# EEPROM_FLASH.net
KiCad netlist of a schematic drawn in Altium Designer
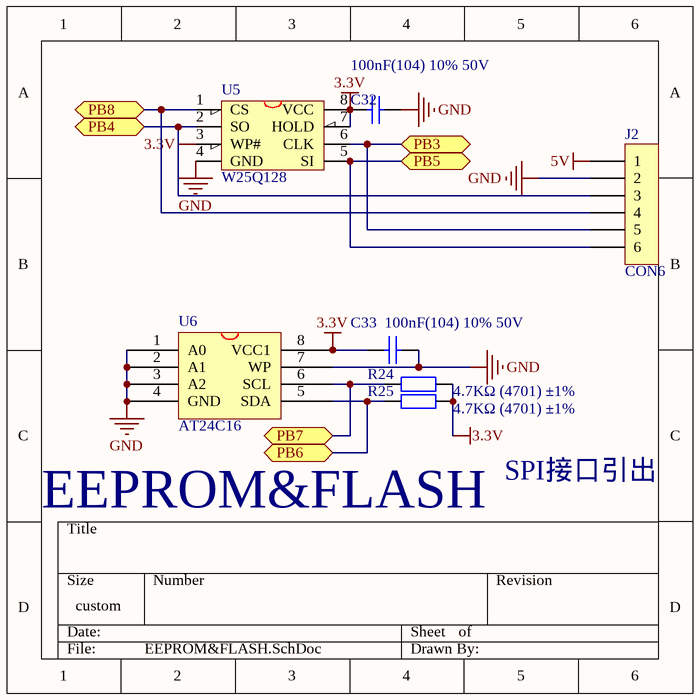
[diagram p0: EEPROM&FLASH.SchDoc]

(export (version "E")
  (design (tool "Eeschema 10.0.6"))
  (components
    (comp (ref "C32")
      (value "100nF(104) 10% 50V")
      (footprint "0805_C")
      (description "贴片电容")
      (libsource (lib "Cap") (part "0805 100nF(104) 10% 50V"))
    )
    (comp (ref "C33")
      (value "100nF(104) 10% 50V")
      (footprint "0805_C")
      (description "贴片电容")
      (libsource (lib "Cap") (part "0805 100nF(104) 10% 50V"))
    )
    (comp (ref "J2")
      (value "CON6")
      (footprint "Connector:XH2.54-6P")
      (description "连接器")
      (libsource (lib "Connector") (part "CON6"))
    )
    (comp (ref "R24")
      (value "4.7KΩ (4701) ±1%")
      (footprint "0805_R")
      (description "贴片电阻")
      (libsource (lib "RES") (part "0805 4.7KΩ (4701) 1%"))
    )
    (comp (ref "R25")
      (value "4.7KΩ (4701) ±1%")
      (footprint "0805_R")
      (description "贴片电阻")
      (libsource (lib "RES") (part "0805 4.7KΩ (4701) 1%"))
    )
    (comp (ref "U5")
      (value "W25Q128")
      (footprint "SOIC-8")
      (description "W25X16;SST25VF016;MX25L1605")
      (libsource (lib "EXPLORER") (part "W25X16"))
    )
    (comp (ref "U6") (value "AT24C16") (footprint "SOP-8") (libsource (lib "EXPLORER") (part "24C256")))
  )
  (nets
    (net (code "1") (name "/PB3") (class "Default")
      (node (ref "J2") (pin "5") (pinfunction "5_5") (pintype "passive"))
      (node (ref "U5") (pin "6") (pinfunction "CLK_6") (pintype "passive"))
    )
    (net (code "2") (name "/PB4") (class "Default")
      (node (ref "J2") (pin "3") (pinfunction "3_3") (pintype "passive"))
      (node (ref "U5") (pin "2") (pinfunction "SO_2") (pintype "passive"))
    )
    (net (code "3") (name "/PB5") (class "Default")
      (node (ref "J2") (pin "6") (pinfunction "6_6") (pintype "passive"))
      (node (ref "U5") (pin "5") (pinfunction "SI_5") (pintype "passive"))
    )
    (net (code "4") (name "/PB6") (class "Default")
      (node (ref "R25") (pin "1") (pinfunction "1_1") (pintype "passive"))
      (node (ref "U6") (pin "5") (pinfunction "SDA_5") (pintype "passive"))
    )
    (net (code "5") (name "/PB7") (class "Default")
      (node (ref "R24") (pin "1") (pinfunction "1_1") (pintype "passive"))
      (node (ref "U6") (pin "6") (pinfunction "SCL_6") (pintype "passive"))
    )
    (net (code "6") (name "/PB8") (class "Default")
      (node (ref "J2") (pin "4") (pinfunction "4_4") (pintype "passive"))
      (node (ref "U5") (pin "1") (pinfunction "CS_1") (pintype "passive"))
    )
    (net (code "7") (name "3.3V") (class "Default")
      (node (ref "C32") (pin "1") (pinfunction "1_1") (pintype "passive"))
      (node (ref "C33") (pin "1") (pinfunction "1_1") (pintype "passive"))
      (node (ref "R24") (pin "2") (pinfunction "2_2") (pintype "passive"))
      (node (ref "R25") (pin "2") (pinfunction "2_2") (pintype "passive"))
      (node (ref "U5") (pin "3") (pinfunction "WP#_3") (pintype "passive"))
      (node (ref "U5") (pin "7") (pinfunction "HOLD_7") (pintype "passive"))
      (node (ref "U5") (pin "8") (pinfunction "VCC_8") (pintype "passive"))
      (node (ref "U6") (pin "8") (pinfunction "VCC1_8") (pintype "passive"))
    )
    (net (code "8") (name "5V") (class "Default")
      (node (ref "J2") (pin "1") (pinfunction "1_1") (pintype "passive"))
    )
    (net (code "9") (name "GND") (class "Default")
      (node (ref "C32") (pin "2") (pinfunction "2_2") (pintype "passive"))
      (node (ref "C33") (pin "2") (pinfunction "2_2") (pintype "passive"))
      (node (ref "J2") (pin "2") (pinfunction "2_2") (pintype "passive"))
      (node (ref "U5") (pin "4") (pinfunction "GND_4") (pintype "passive"))
      (node (ref "U6") (pin "1") (pinfunction "A0_1") (pintype "passive"))
      (node (ref "U6") (pin "2") (pinfunction "A1_2") (pintype "passive"))
      (node (ref "U6") (pin "3") (pinfunction "A2_3") (pintype "passive"))
      (node (ref "U6") (pin "4") (pinfunction "GND_4") (pintype "passive"))
      (node (ref "U6") (pin "7") (pinfunction "WP_7") (pintype "passive"))
    )
  )
)
